# xmos.net
KiCad netlist of a schematic drawn in Altium Designer
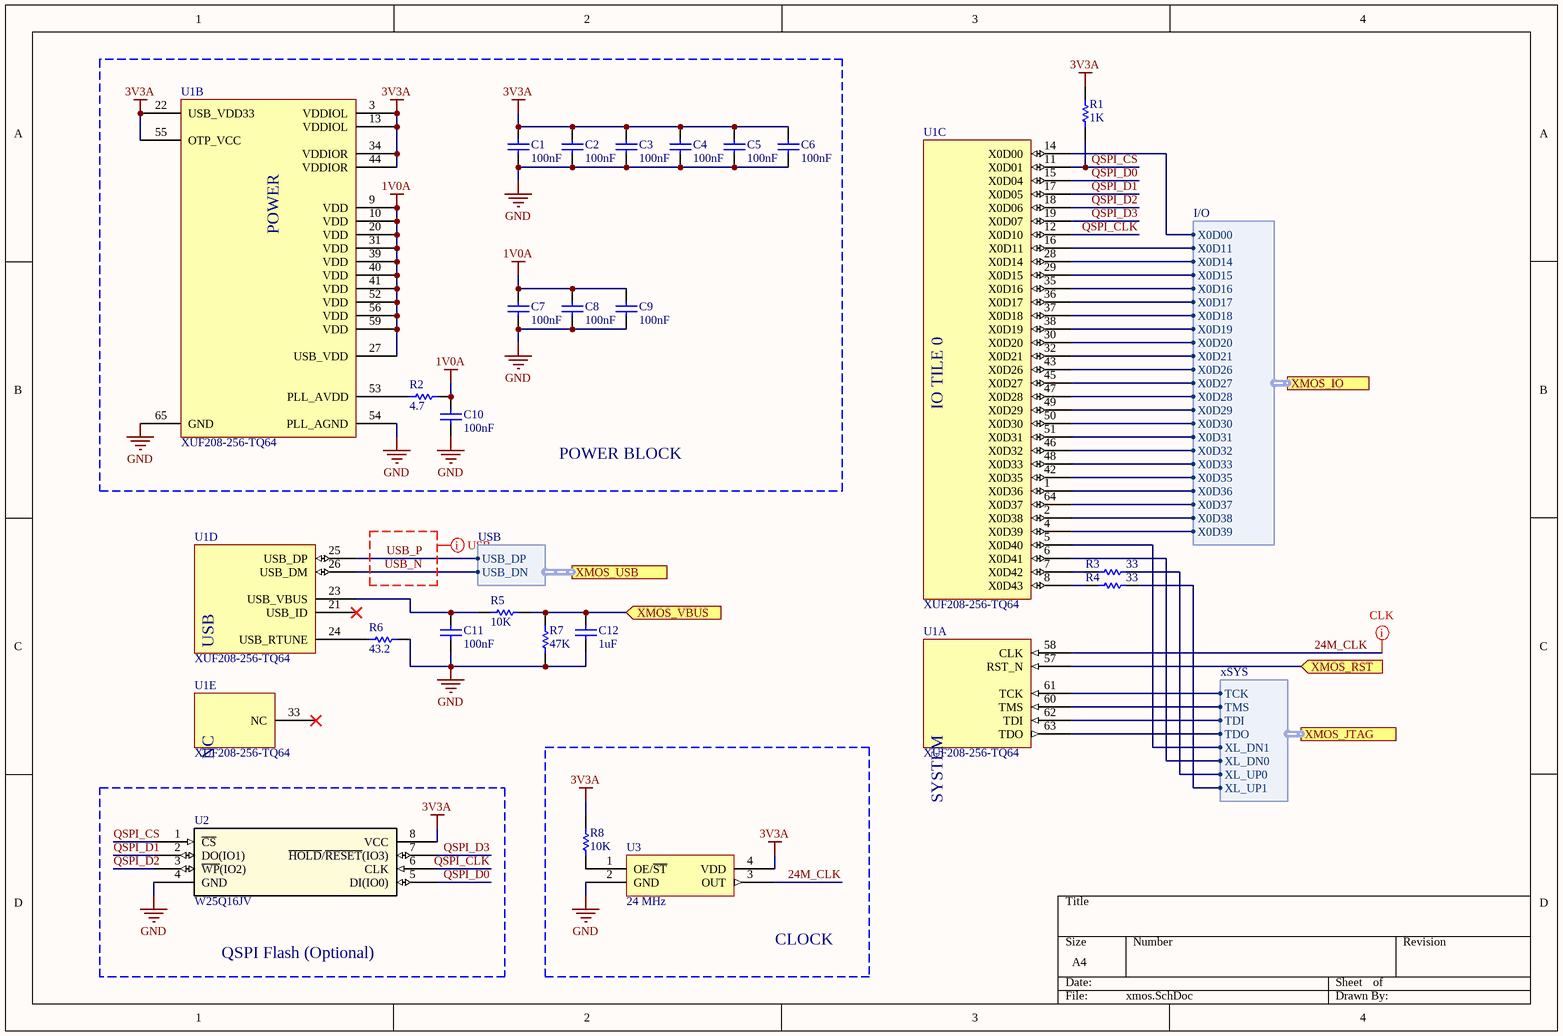
[diagram p0: xmos.SchDoc]

(export (version "E")
  (design (tool "Eeschema 10.0.6"))
  (components
    (comp (ref "C1")
      (value "100nF")
      (footprint "CAP_0603")
      (description "Multilayer Ceramic Capacitors")
      (fields (field (name "TOLERANCE") "10%") (field (name "Comment") "MLCC"))
      (libsource (lib "Capacitors") (part "MLCC"))
    )
    (comp (ref "C2")
      (value "100nF")
      (footprint "CAP_0603")
      (description "Multilayer Ceramic Capacitors")
      (fields (field (name "TOLERANCE") "10%") (field (name "Comment") "MLCC"))
      (libsource (lib "Capacitors") (part "MLCC"))
    )
    (comp (ref "C3")
      (value "100nF")
      (footprint "CAP_0603")
      (description "Multilayer Ceramic Capacitors")
      (fields (field (name "TOLERANCE") "10%") (field (name "Comment") "MLCC"))
      (libsource (lib "Capacitors") (part "MLCC"))
    )
    (comp (ref "C4")
      (value "100nF")
      (footprint "CAP_0603")
      (description "Multilayer Ceramic Capacitors")
      (fields (field (name "TOLERANCE") "10%") (field (name "Comment") "MLCC"))
      (libsource (lib "Capacitors") (part "MLCC"))
    )
    (comp (ref "C5")
      (value "100nF")
      (footprint "CAP_0603")
      (description "Multilayer Ceramic Capacitors")
      (fields (field (name "TOLERANCE") "10%") (field (name "Comment") "MLCC"))
      (libsource (lib "Capacitors") (part "MLCC"))
    )
    (comp (ref "C6")
      (value "100nF")
      (footprint "CAP_0603")
      (description "Multilayer Ceramic Capacitors")
      (fields (field (name "TOLERANCE") "10%") (field (name "Comment") "MLCC"))
      (libsource (lib "Capacitors") (part "MLCC"))
    )
    (comp (ref "C7")
      (value "100nF")
      (footprint "CAP_0603")
      (description "Multilayer Ceramic Capacitors")
      (fields (field (name "TOLERANCE") "10%") (field (name "Comment") "MLCC"))
      (libsource (lib "Capacitors") (part "MLCC"))
    )
    (comp (ref "C8")
      (value "100nF")
      (footprint "CAP_0603")
      (description "Multilayer Ceramic Capacitors")
      (fields (field (name "TOLERANCE") "10%") (field (name "Comment") "MLCC"))
      (libsource (lib "Capacitors") (part "MLCC"))
    )
    (comp (ref "C9")
      (value "100nF")
      (footprint "CAP_0603")
      (description "Multilayer Ceramic Capacitors")
      (fields (field (name "TOLERANCE") "10%") (field (name "Comment") "MLCC"))
      (libsource (lib "Capacitors") (part "MLCC"))
    )
    (comp (ref "C10")
      (value "100nF")
      (footprint "CAP_0603")
      (description "Multilayer Ceramic Capacitors")
      (fields (field (name "TOLERANCE") "10%") (field (name "Comment") "MLCC"))
      (libsource (lib "Capacitors") (part "MLCC"))
    )
    (comp (ref "C11")
      (value "100nF")
      (footprint "CAP_0603")
      (description "Multilayer Ceramic Capacitors")
      (fields (field (name "TOLERANCE") "10%") (field (name "Comment") "MLCC"))
      (libsource (lib "Capacitors") (part "MLCC"))
    )
    (comp (ref "C12")
      (value "1uF")
      (footprint "CAP_0603")
      (description "Multilayer Ceramic Capacitors")
      (fields (field (name "TOLERANCE") "10%") (field (name "Comment") "MLCC"))
      (libsource (lib "Capacitors") (part "MLCC"))
    )
    (comp (ref "R1")
      (value "1K")
      (footprint "RC0603N")
      (description "Chip Resistors")
      (fields (field (name "Comment") "RES"))
      (libsource (lib "Resistors") (part "RES"))
    )
    (comp (ref "R2")
      (value "4.7")
      (footprint "RC0603N")
      (description "Chip Resistors")
      (fields (field (name "Comment") "RES"))
      (libsource (lib "Resistors") (part "RES"))
    )
    (comp (ref "R3")
      (value "33")
      (footprint "RC0603N")
      (description "Chip Resistors")
      (fields (field (name "Comment") "RES"))
      (libsource (lib "Resistors") (part "RES"))
    )
    (comp (ref "R4")
      (value "33")
      (footprint "RC0603N")
      (description "Chip Resistors")
      (fields (field (name "Comment") "RES"))
      (libsource (lib "Resistors") (part "RES"))
    )
    (comp (ref "R5")
      (value "10K")
      (footprint "RC0603N")
      (description "Chip Resistors")
      (fields (field (name "Comment") "RES"))
      (libsource (lib "Resistors") (part "RES"))
    )
    (comp (ref "R6")
      (value "43.2")
      (footprint "RC0603N")
      (description "Chip Resistors")
      (fields (field (name "Comment") "RES"))
      (libsource (lib "Resistors") (part "RES"))
    )
    (comp (ref "R7")
      (value "47K")
      (footprint "RC0603N")
      (description "Chip Resistors")
      (fields (field (name "Comment") "RES"))
      (libsource (lib "Resistors") (part "RES"))
    )
    (comp (ref "R8")
      (value "10K")
      (footprint "RC0603N")
      (description "Chip Resistors")
      (fields (field (name "Comment") "RES"))
      (libsource (lib "Resistors") (part "RES"))
    )
    (comp (ref "U1")
      (value "XUF208-256-TQ64")
      (footprint "TQ64")
      (description "xCORE Multicore Microcontroller, xCORE-200, USB, Single Tile, 8 Cores, 500MHz, 64TQFP")
      (fields (field (name "MANUFACTURER") "XMOS"))
      (libsource (lib "") (part "XUF208-256-TQ64_1"))
    )
    (comp (ref "U2")
      (value "W25Q16JV")
      (footprint "SOIC-8_150MIL")
      (description "3V 16M-BIT SERIAL FLASH MEMORY WITH DUAL/QUAD SPI")
      (fields
        (field (name "MANUFACTURER_PART_NUMBER") "W25Q16JVXXXX")
        (field (name "COPYRIGHT") "Copyright (C) 2018 Accelerated Designs. All rights reserved")
      )
      (libsource (lib "WINBOND") (part "W25Q16JV"))
    )
    (comp (ref "U3")
      (value "XO")
      (footprint "QFN_3225_4P")
      (description "SiTime Ultra Performance Oscillator")
      (fields (field (name "MANUFACTURER") "SiTime") (field (name "FREQUENCY") "24 MHz"))
      (libsource (lib "Crystals") (part "XO"))
    )
  )
  (nets
    (net (code "4") (name "/24M_CLK") (class "Default")
      (node (ref "U1") (pin "58") (pinfunction "CLK_58") (pintype "input"))
      (node (ref "U3") (pin "3") (pinfunction "OUT_3") (pintype "output"))
    )
    (net (code "5") (name "/QSPI_CLK") (class "Default")
      (node (ref "U1") (pin "12") (pinfunction "X0D10_12") (pintype "bidirectional"))
      (node (ref "U2") (pin "6") (pinfunction "CLK_6") (pintype "input"))
    )
    (net (code "6") (name "/QSPI_CS") (class "Default")
      (node (ref "R1") (pin "1") (pinfunction "1_1") (pintype "passive"))
      (node (ref "U1") (pin "11") (pinfunction "X0D01_11") (pintype "bidirectional"))
      (node (ref "U2") (pin "1") (pinfunction "~{CS}_1") (pintype "input"))
    )
    (net (code "7") (name "/QSPI_D0") (class "Default")
      (node (ref "U1") (pin "15") (pinfunction "X0D04_15") (pintype "bidirectional"))
      (node (ref "U2") (pin "5") (pinfunction "DI(IO0)_5") (pintype "bidirectional"))
    )
    (net (code "8") (name "/QSPI_D1") (class "Default")
      (node (ref "U1") (pin "17") (pinfunction "X0D05_17") (pintype "bidirectional"))
      (node (ref "U2") (pin "2") (pinfunction "DO(IO1)_2") (pintype "bidirectional"))
    )
    (net (code "9") (name "/QSPI_D2") (class "Default")
      (node (ref "U1") (pin "18") (pinfunction "X0D06_18") (pintype "bidirectional"))
      (node (ref "U2") (pin "3") (pinfunction "~{WP}(IO2)_3") (pintype "bidirectional"))
    )
    (net (code "10") (name "/QSPI_D3") (class "Default")
      (node (ref "U1") (pin "19") (pinfunction "X0D07_19") (pintype "bidirectional"))
      (node (ref "U2") (pin "7") (pinfunction "~{HOLD}/~{RESET}(IO3)_7") (pintype "bidirectional"))
    )
    (net (code "11") (name "/TCK") (class "Default")
      (node (ref "U1") (pin "61") (pinfunction "TCK_61") (pintype "input"))
    )
    (net (code "12") (name "/TDI") (class "Default")
      (node (ref "U1") (pin "62") (pinfunction "TDI_62") (pintype "input"))
    )
    (net (code "13") (name "/TDO") (class "Default")
      (node (ref "U1") (pin "63") (pinfunction "TDO_63") (pintype "output"))
    )
    (net (code "14") (name "/TMS") (class "Default")
      (node (ref "U1") (pin "60") (pinfunction "TMS_60") (pintype "input"))
    )
    (net (code "15") (name "/USB_N") (class "Default")
      (node (ref "U1") (pin "26") (pinfunction "USB_DM_26") (pintype "bidirectional"))
    )
    (net (code "16") (name "/USB_P") (class "Default")
      (node (ref "U1") (pin "25") (pinfunction "USB_DP_25") (pintype "bidirectional"))
    )
    (net (code "17") (name "/X0D00") (class "Default")
      (node (ref "U1") (pin "14") (pinfunction "X0D00_14") (pintype "bidirectional"))
    )
    (net (code "18") (name "/X0D11") (class "Default")
      (node (ref "U1") (pin "16") (pinfunction "X0D11_16") (pintype "bidirectional"))
    )
    (net (code "19") (name "/X0D14") (class "Default")
      (node (ref "U1") (pin "28") (pinfunction "X0D14_28") (pintype "bidirectional"))
    )
    (net (code "20") (name "/X0D15") (class "Default")
      (node (ref "U1") (pin "29") (pinfunction "X0D15_29") (pintype "bidirectional"))
    )
    (net (code "21") (name "/X0D16") (class "Default")
      (node (ref "U1") (pin "35") (pinfunction "X0D16_35") (pintype "bidirectional"))
    )
    (net (code "22") (name "/X0D17") (class "Default")
      (node (ref "U1") (pin "36") (pinfunction "X0D17_36") (pintype "bidirectional"))
    )
    (net (code "23") (name "/X0D18") (class "Default")
      (node (ref "U1") (pin "37") (pinfunction "X0D18_37") (pintype "bidirectional"))
    )
    (net (code "24") (name "/X0D19") (class "Default")
      (node (ref "U1") (pin "38") (pinfunction "X0D19_38") (pintype "bidirectional"))
    )
    (net (code "25") (name "/X0D20") (class "Default")
      (node (ref "U1") (pin "30") (pinfunction "X0D20_30") (pintype "bidirectional"))
    )
    (net (code "26") (name "/X0D21") (class "Default")
      (node (ref "U1") (pin "32") (pinfunction "X0D21_32") (pintype "bidirectional"))
    )
    (net (code "27") (name "/X0D26") (class "Default")
      (node (ref "U1") (pin "43") (pinfunction "X0D26_43") (pintype "bidirectional"))
    )
    (net (code "28") (name "/X0D27") (class "Default")
      (node (ref "U1") (pin "45") (pinfunction "X0D27_45") (pintype "bidirectional"))
    )
    (net (code "29") (name "/X0D28") (class "Default")
      (node (ref "U1") (pin "47") (pinfunction "X0D28_47") (pintype "bidirectional"))
    )
    (net (code "30") (name "/X0D29") (class "Default")
      (node (ref "U1") (pin "49") (pinfunction "X0D29_49") (pintype "bidirectional"))
    )
    (net (code "31") (name "/X0D30") (class "Default")
      (node (ref "U1") (pin "50") (pinfunction "X0D30_50") (pintype "bidirectional"))
    )
    (net (code "32") (name "/X0D31") (class "Default")
      (node (ref "U1") (pin "51") (pinfunction "X0D31_51") (pintype "bidirectional"))
    )
    (net (code "33") (name "/X0D32") (class "Default")
      (node (ref "U1") (pin "46") (pinfunction "X0D32_46") (pintype "bidirectional"))
    )
    (net (code "34") (name "/X0D33") (class "Default")
      (node (ref "U1") (pin "48") (pinfunction "X0D33_48") (pintype "bidirectional"))
    )
    (net (code "35") (name "/X0D35") (class "Default")
      (node (ref "U1") (pin "42") (pinfunction "X0D35_42") (pintype "bidirectional"))
    )
    (net (code "36") (name "/X0D36") (class "Default")
      (node (ref "U1") (pin "1") (pinfunction "X0D36_1") (pintype "bidirectional"))
    )
    (net (code "37") (name "/X0D37") (class "Default")
      (node (ref "U1") (pin "64") (pinfunction "X0D37_64") (pintype "bidirectional"))
    )
    (net (code "38") (name "/X0D38") (class "Default")
      (node (ref "U1") (pin "2") (pinfunction "X0D38_2") (pintype "bidirectional"))
    )
    (net (code "39") (name "/X0D39") (class "Default")
      (node (ref "U1") (pin "4") (pinfunction "X0D39_4") (pintype "bidirectional"))
    )
    (net (code "40") (name "/XL_DN0") (class "Default")
      (node (ref "U1") (pin "6") (pinfunction "X0D41_6") (pintype "bidirectional"))
    )
    (net (code "41") (name "/XL_DN1") (class "Default")
      (node (ref "U1") (pin "5") (pinfunction "X0D40_5") (pintype "bidirectional"))
    )
    (net (code "42") (name "/XL_UP0") (class "Default")
      (node (ref "R3") (pin "2") (pinfunction "2_2") (pintype "passive"))
    )
    (net (code "43") (name "/XL_UP1") (class "Default")
      (node (ref "R4") (pin "2") (pinfunction "2_2") (pintype "passive"))
    )
    (net (code "44") (name "/XMOS_RST") (class "Default")
      (node (ref "U1") (pin "57") (pinfunction "RST_N_57") (pintype "input"))
    )
    (net (code "45") (name "/XMOS_VBUS") (class "Default")
      (node (ref "C12") (pin "1") (pinfunction "1_1") (pintype "passive"))
      (node (ref "R5") (pin "2") (pinfunction "2_2") (pintype "passive"))
      (node (ref "R7") (pin "2") (pinfunction "2_2") (pintype "passive"))
    )
    (net (code "49") (name "1V0A") (class "Default")
      (node (ref "C10") (pin "2") (pinfunction "2_2") (pintype "passive"))
      (node (ref "C7") (pin "2") (pinfunction "2_2") (pintype "passive"))
      (node (ref "C8") (pin "2") (pinfunction "2_2") (pintype "passive"))
      (node (ref "C9") (pin "2") (pinfunction "2_2") (pintype "passive"))
      (node (ref "R2") (pin "2") (pinfunction "2_2") (pintype "passive"))
      (node (ref "U1") (pin "10") (pinfunction "VDD_10") (pintype "power_in"))
      (node (ref "U1") (pin "20") (pinfunction "VDD_20") (pintype "power_in"))
      (node (ref "U1") (pin "27") (pinfunction "USB_VDD_27") (pintype "power_in"))
      (node (ref "U1") (pin "31") (pinfunction "VDD_31") (pintype "power_in"))
      (node (ref "U1") (pin "39") (pinfunction "VDD_39") (pintype "power_in"))
      (node (ref "U1") (pin "40") (pinfunction "VDD_40") (pintype "power_in"))
      (node (ref "U1") (pin "41") (pinfunction "VDD_41") (pintype "power_in"))
      (node (ref "U1") (pin "52") (pinfunction "VDD_52") (pintype "power_in"))
      (node (ref "U1") (pin "56") (pinfunction "VDD_56") (pintype "power_in"))
      (node (ref "U1") (pin "59") (pinfunction "VDD_59") (pintype "power_in"))
      (node (ref "U1") (pin "9") (pinfunction "VDD_9") (pintype "power_in"))
    )
    (net (code "50") (name "3V3A") (class "Default")
      (node (ref "C1") (pin "2") (pinfunction "2_2") (pintype "passive"))
      (node (ref "C2") (pin "2") (pinfunction "2_2") (pintype "passive"))
      (node (ref "C3") (pin "2") (pinfunction "2_2") (pintype "passive"))
      (node (ref "C4") (pin "2") (pinfunction "2_2") (pintype "passive"))
      (node (ref "C5") (pin "2") (pinfunction "2_2") (pintype "passive"))
      (node (ref "C6") (pin "2") (pinfunction "2_2") (pintype "passive"))
      (node (ref "R1") (pin "2") (pinfunction "2_2") (pintype "passive"))
      (node (ref "R8") (pin "2") (pinfunction "2_2") (pintype "passive"))
      (node (ref "U1") (pin "13") (pinfunction "VDDIOL_13") (pintype "power_in"))
      (node (ref "U1") (pin "22") (pinfunction "USB_VDD33_22") (pintype "power_in"))
      (node (ref "U1") (pin "3") (pinfunction "VDDIOL_3") (pintype "power_in"))
      (node (ref "U1") (pin "34") (pinfunction "VDDIOR_34") (pintype "power_in"))
      (node (ref "U1") (pin "44") (pinfunction "VDDIOR_44") (pintype "power_in"))
      (node (ref "U1") (pin "55") (pinfunction "OTP_VCC_55") (pintype "power_in"))
      (node (ref "U2") (pin "8") (pinfunction "VCC_8") (pintype "power_in"))
      (node (ref "U3") (pin "4") (pinfunction "VDD_4") (pintype "power_in"))
    )
    (net (code "51") (name "GND") (class "Default")
      (node (ref "C1") (pin "1") (pinfunction "1_1") (pintype "passive"))
      (node (ref "C10") (pin "1") (pinfunction "1_1") (pintype "passive"))
      (node (ref "C11") (pin "1") (pinfunction "1_1") (pintype "passive"))
      (node (ref "C12") (pin "2") (pinfunction "2_2") (pintype "passive"))
      (node (ref "C2") (pin "1") (pinfunction "1_1") (pintype "passive"))
      (node (ref "C3") (pin "1") (pinfunction "1_1") (pintype "passive"))
      (node (ref "C4") (pin "1") (pinfunction "1_1") (pintype "passive"))
      (node (ref "C5") (pin "1") (pinfunction "1_1") (pintype "passive"))
      (node (ref "C6") (pin "1") (pinfunction "1_1") (pintype "passive"))
      (node (ref "C7") (pin "1") (pinfunction "1_1") (pintype "passive"))
      (node (ref "C8") (pin "1") (pinfunction "1_1") (pintype "passive"))
      (node (ref "C9") (pin "1") (pinfunction "1_1") (pintype "passive"))
      (node (ref "R6") (pin "2") (pinfunction "2_2") (pintype "passive"))
      (node (ref "R7") (pin "1") (pinfunction "1_1") (pintype "passive"))
      (node (ref "U1") (pin "54") (pinfunction "PLL_AGND_54") (pintype "power_in"))
      (node (ref "U1") (pin "65") (pinfunction "GND_65") (pintype "power_in"))
      (node (ref "U2") (pin "4") (pinfunction "GND_4") (pintype "passive"))
      (node (ref "U3") (pin "2") (pinfunction "GND_2") (pintype "passive"))
    )
    (net (code "52") (name "Net-(U1B-PLL_AVDD)") (class "Default")
      (node (ref "R2") (pin "1") (pinfunction "1_1") (pintype "passive"))
      (node (ref "U1") (pin "53") (pinfunction "PLL_AVDD_53") (pintype "power_in"))
    )
    (net (code "53") (name "Net-(U1C-X0D42)") (class "Default")
      (node (ref "R3") (pin "1") (pinfunction "1_1") (pintype "passive"))
      (node (ref "U1") (pin "7") (pinfunction "X0D42_7") (pintype "bidirectional"))
    )
    (net (code "54") (name "Net-(U1C-X0D43)") (class "Default")
      (node (ref "R4") (pin "1") (pinfunction "1_1") (pintype "passive"))
      (node (ref "U1") (pin "8") (pinfunction "X0D43_8") (pintype "bidirectional"))
    )
    (net (code "55") (name "Net-(U1D-USB_RTUNE)") (class "Default")
      (node (ref "R6") (pin "1") (pinfunction "1_1") (pintype "passive"))
      (node (ref "U1") (pin "24") (pinfunction "USB_RTUNE_24") (pintype "passive"))
    )
    (net (code "56") (name "Net-(U1D-USB_VBUS)") (class "Default")
      (node (ref "C11") (pin "2") (pinfunction "2_2") (pintype "passive"))
      (node (ref "R5") (pin "1") (pinfunction "1_1") (pintype "passive"))
      (node (ref "U1") (pin "23") (pinfunction "USB_VBUS_23") (pintype "passive"))
    )
    (net (code "57") (name "Net-(U3-OE{slash}~{ST})") (class "Default")
      (node (ref "R8") (pin "1") (pinfunction "1_1") (pintype "passive"))
      (node (ref "U3") (pin "1") (pinfunction "OE/~{ST}_1") (pintype "passive"))
    )
    (net (code "58") (name "unconnected-(U1D-USB_ID-Pad21)") (class "Default")
      (node (ref "U1") (pin "21") (pinfunction "USB_ID_21") (pintype "passive+no_connect"))
    )
    (net (code "59") (name "unconnected-(U1E-NC-Pad33)") (class "Default")
      (node (ref "U1") (pin "33") (pinfunction "NC_33") (pintype "passive+no_connect"))
    )
  )
)
